# Or_ing.net
KiCad netlist of a schematic drawn in EAGLE
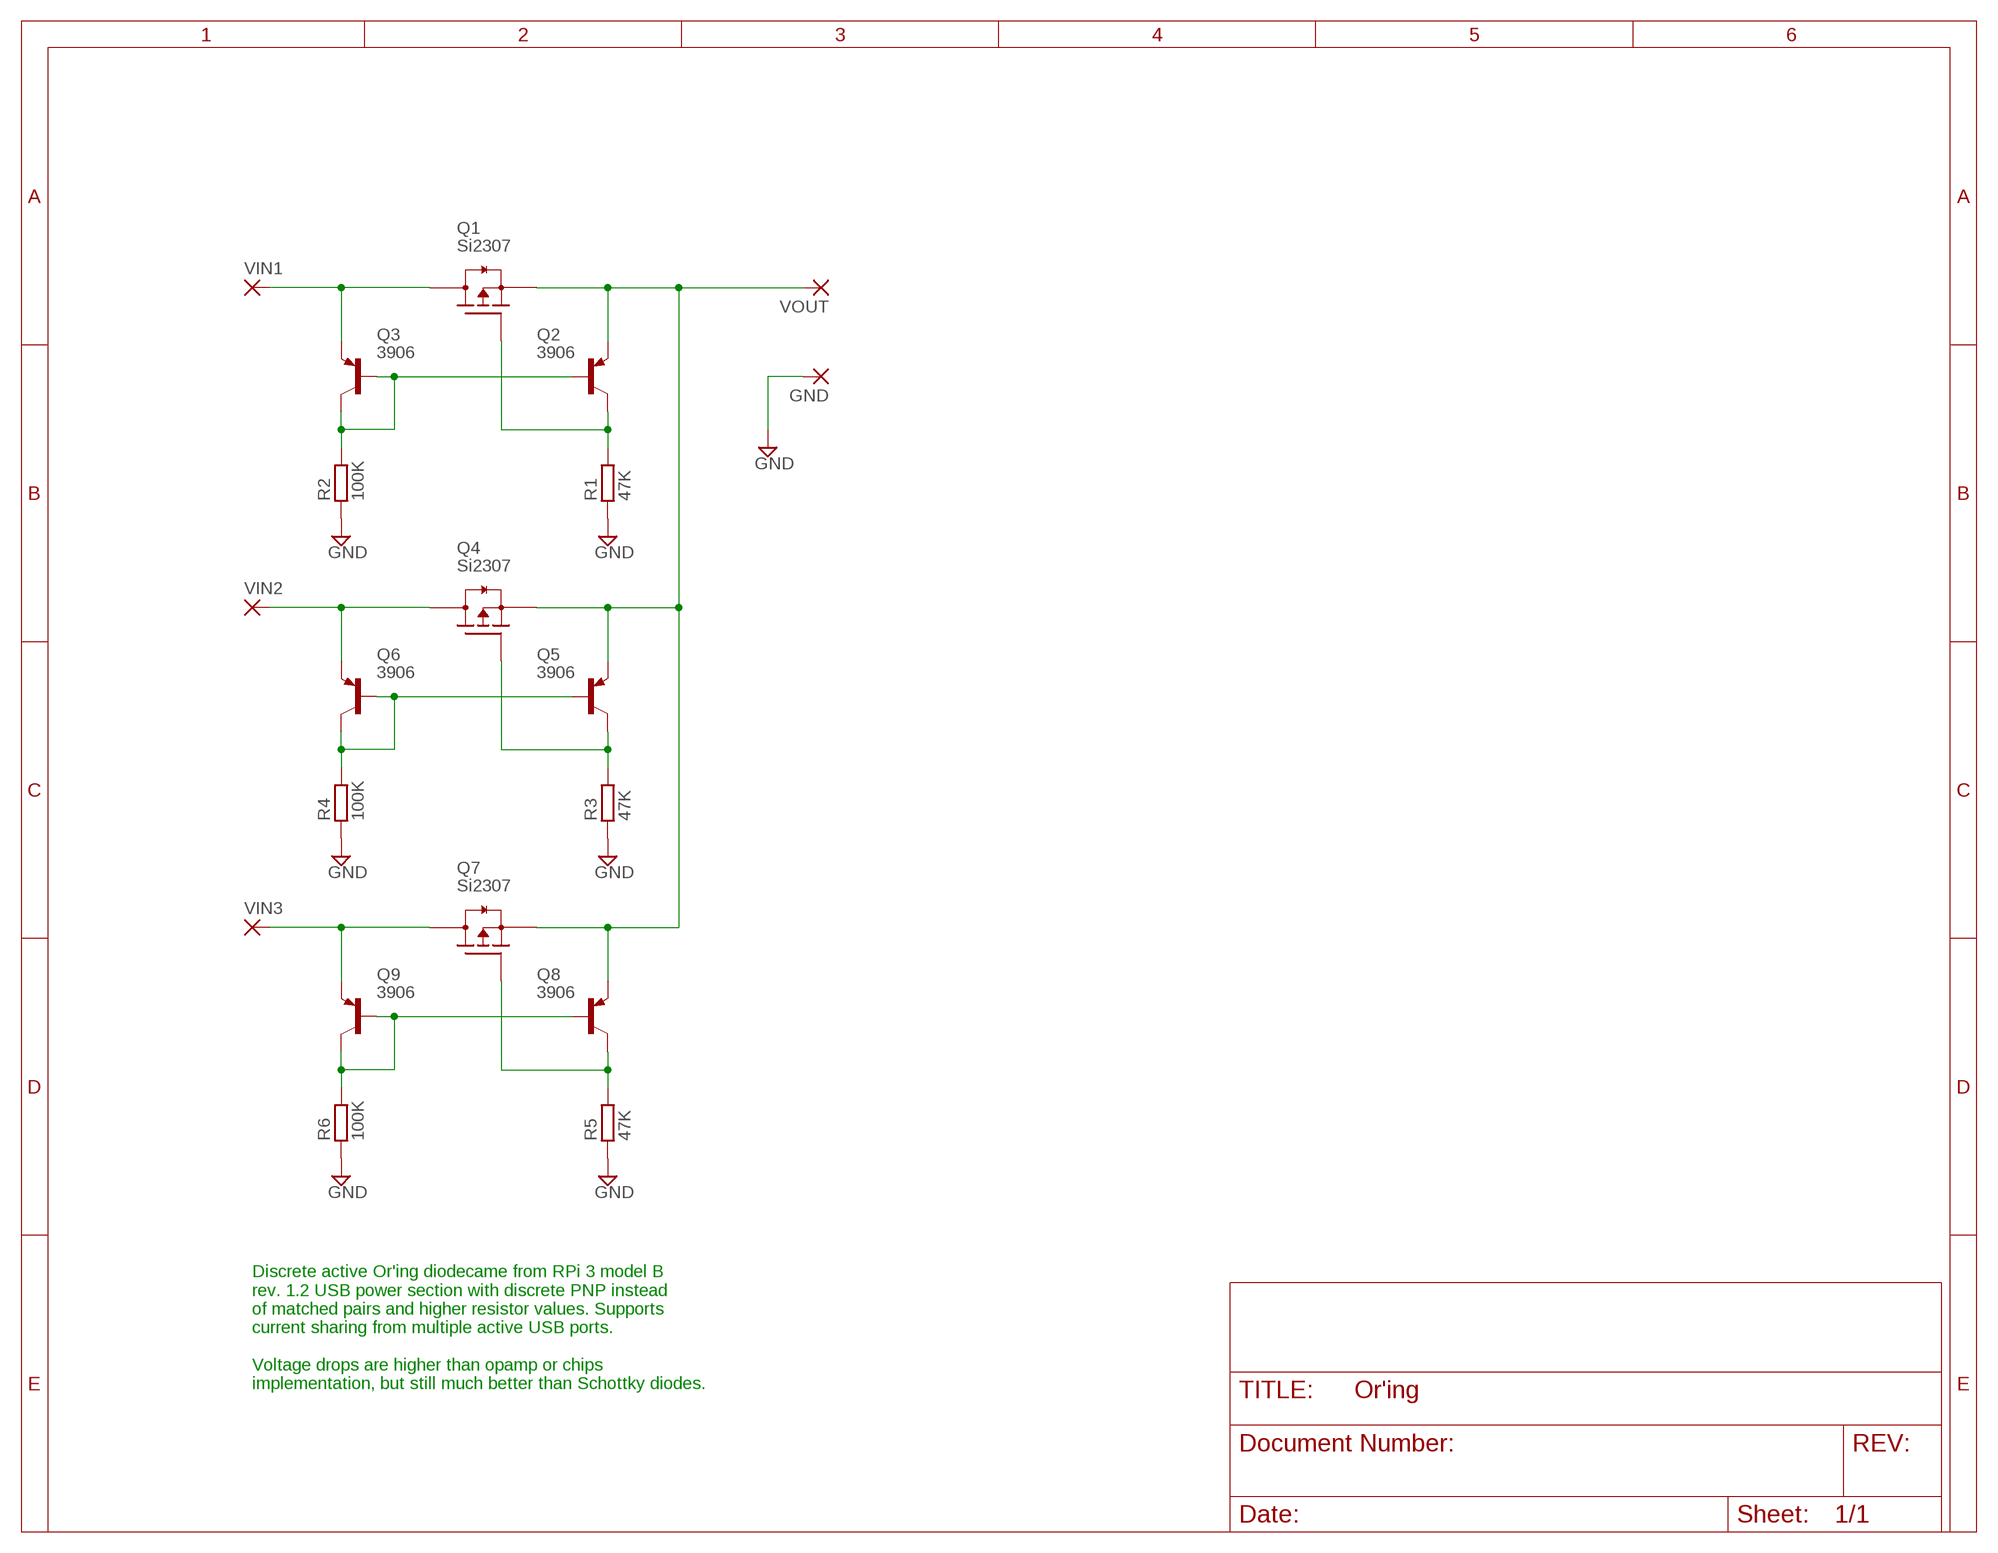
[diagram p0: schematic, sheet 1]

(export (version "E")
  (design (tool "Eeschema 10.0.6"))
  (components
    (comp (ref "GND")
      (value "SMD2")
      (footprint "eagle-import:SMD1,27-2,54")
      (libsource (lib "eagle-import") (part "SMD2"))
    )
    (comp (ref "Q1")
      (value "Si2307")
      (footprint "eagle-import:SOT95P280X135-3N")
      (libsource (lib "eagle-import") (part "MOSFET-PCH_SOT-23"))
    )
    (comp (ref "Q2")
      (value "3906")
      (footprint "eagle-import:SOT95P280X135-3N")
      (libsource (lib "eagle-import") (part "PNP_SOT-23"))
    )
    (comp (ref "Q3")
      (value "3906")
      (footprint "eagle-import:SOT95P280X135-3N")
      (libsource (lib "eagle-import") (part "PNP_SOT-23"))
    )
    (comp (ref "Q4")
      (value "Si2307")
      (footprint "eagle-import:SOT95P280X135-3N")
      (libsource (lib "eagle-import") (part "MOSFET-PCH_SOT-23"))
    )
    (comp (ref "Q5")
      (value "3906")
      (footprint "eagle-import:SOT95P280X135-3N")
      (libsource (lib "eagle-import") (part "PNP_SOT-23"))
    )
    (comp (ref "Q6")
      (value "3906")
      (footprint "eagle-import:SOT95P280X135-3N")
      (libsource (lib "eagle-import") (part "PNP_SOT-23"))
    )
    (comp (ref "Q7")
      (value "Si2307")
      (footprint "eagle-import:SOT95P280X135-3N")
      (libsource (lib "eagle-import") (part "MOSFET-PCH_SOT-23"))
    )
    (comp (ref "Q8")
      (value "3906")
      (footprint "eagle-import:SOT95P280X135-3N")
      (libsource (lib "eagle-import") (part "PNP_SOT-23"))
    )
    (comp (ref "Q9")
      (value "3906")
      (footprint "eagle-import:SOT95P280X135-3N")
      (libsource (lib "eagle-import") (part "PNP_SOT-23"))
    )
    (comp (ref "R1")
      (value "47K")
      (footprint "eagle-import:RESC1608X55N")
      (libsource (lib "eagle-import") (part "RESISTOR_0603"))
    )
    (comp (ref "R2")
      (value "100K")
      (footprint "eagle-import:RESC1608X55N")
      (libsource (lib "eagle-import") (part "RESISTOR_0603"))
    )
    (comp (ref "R3")
      (value "47K")
      (footprint "eagle-import:RESC1608X55N")
      (libsource (lib "eagle-import") (part "RESISTOR_0603"))
    )
    (comp (ref "R4")
      (value "100K")
      (footprint "eagle-import:RESC1608X55N")
      (libsource (lib "eagle-import") (part "RESISTOR_0603"))
    )
    (comp (ref "R5")
      (value "47K")
      (footprint "eagle-import:RESC1608X55N")
      (libsource (lib "eagle-import") (part "RESISTOR_0603"))
    )
    (comp (ref "R6")
      (value "100K")
      (footprint "eagle-import:RESC1608X55N")
      (libsource (lib "eagle-import") (part "RESISTOR_0603"))
    )
    (comp (ref "VIN1")
      (value "SMD2")
      (footprint "eagle-import:SMD1,27-2,54")
      (libsource (lib "eagle-import") (part "SMD2"))
    )
    (comp (ref "VIN2")
      (value "SMD2")
      (footprint "eagle-import:SMD1,27-2,54")
      (libsource (lib "eagle-import") (part "SMD2"))
    )
    (comp (ref "VIN3")
      (value "SMD2")
      (footprint "eagle-import:SMD1,27-2,54")
      (libsource (lib "eagle-import") (part "SMD2"))
    )
    (comp (ref "VOUT")
      (value "SMD2")
      (footprint "eagle-import:SMD1,27-2,54")
      (libsource (lib "eagle-import") (part "SMD2"))
    )
  )
  (nets
    (net (code "1") (name "GND") (class "Default")
      (node (ref "GND") (pin "1") (pinfunction "P_1") (pintype "passive"))
      (node (ref "R1") (pin "1") (pinfunction "1_1") (pintype "passive"))
      (node (ref "R2") (pin "1") (pinfunction "1_1") (pintype "passive"))
      (node (ref "R3") (pin "1") (pinfunction "1_1") (pintype "passive"))
      (node (ref "R4") (pin "1") (pinfunction "1_1") (pintype "passive"))
      (node (ref "R5") (pin "1") (pinfunction "1_1") (pintype "passive"))
      (node (ref "R6") (pin "1") (pinfunction "1_1") (pintype "passive"))
    )
    (net (code "2") (name "Net-(Q1-D)") (class "Default")
      (node (ref "Q1") (pin "3") (pinfunction "D_3") (pintype "passive"))
      (node (ref "Q3") (pin "2") (pinfunction "E_2") (pintype "passive"))
      (node (ref "VIN1") (pin "1") (pinfunction "P_1") (pintype "passive"))
    )
    (net (code "3") (name "Net-(Q1-G)") (class "Default")
      (node (ref "Q1") (pin "1") (pinfunction "G_1") (pintype "passive"))
      (node (ref "Q2") (pin "3") (pinfunction "C_3") (pintype "passive"))
      (node (ref "R1") (pin "2") (pinfunction "2_2") (pintype "passive"))
    )
    (net (code "4") (name "Net-(Q1-S)") (class "Default")
      (node (ref "Q1") (pin "2") (pinfunction "S_2") (pintype "passive"))
      (node (ref "Q2") (pin "2") (pinfunction "E_2") (pintype "passive"))
      (node (ref "Q4") (pin "2") (pinfunction "S_2") (pintype "passive"))
      (node (ref "Q5") (pin "2") (pinfunction "E_2") (pintype "passive"))
      (node (ref "Q7") (pin "2") (pinfunction "S_2") (pintype "passive"))
      (node (ref "Q8") (pin "2") (pinfunction "E_2") (pintype "passive"))
      (node (ref "VOUT") (pin "1") (pinfunction "P_1") (pintype "passive"))
    )
    (net (code "5") (name "Net-(Q2-B)") (class "Default")
      (node (ref "Q2") (pin "1") (pinfunction "B_1") (pintype "passive"))
      (node (ref "Q3") (pin "1") (pinfunction "B_1") (pintype "passive"))
      (node (ref "Q3") (pin "3") (pinfunction "C_3") (pintype "passive"))
      (node (ref "R2") (pin "2") (pinfunction "2_2") (pintype "passive"))
    )
    (net (code "6") (name "Net-(Q4-D)") (class "Default")
      (node (ref "Q4") (pin "3") (pinfunction "D_3") (pintype "passive"))
      (node (ref "Q6") (pin "2") (pinfunction "E_2") (pintype "passive"))
      (node (ref "VIN2") (pin "1") (pinfunction "P_1") (pintype "passive"))
    )
    (net (code "7") (name "Net-(Q4-G)") (class "Default")
      (node (ref "Q4") (pin "1") (pinfunction "G_1") (pintype "passive"))
      (node (ref "Q5") (pin "3") (pinfunction "C_3") (pintype "passive"))
      (node (ref "R3") (pin "2") (pinfunction "2_2") (pintype "passive"))
    )
    (net (code "8") (name "Net-(Q5-B)") (class "Default")
      (node (ref "Q5") (pin "1") (pinfunction "B_1") (pintype "passive"))
      (node (ref "Q6") (pin "1") (pinfunction "B_1") (pintype "passive"))
      (node (ref "Q6") (pin "3") (pinfunction "C_3") (pintype "passive"))
      (node (ref "R4") (pin "2") (pinfunction "2_2") (pintype "passive"))
    )
    (net (code "9") (name "Net-(Q7-D)") (class "Default")
      (node (ref "Q7") (pin "3") (pinfunction "D_3") (pintype "passive"))
      (node (ref "Q9") (pin "2") (pinfunction "E_2") (pintype "passive"))
      (node (ref "VIN3") (pin "1") (pinfunction "P_1") (pintype "passive"))
    )
    (net (code "10") (name "Net-(Q7-G)") (class "Default")
      (node (ref "Q7") (pin "1") (pinfunction "G_1") (pintype "passive"))
      (node (ref "Q8") (pin "3") (pinfunction "C_3") (pintype "passive"))
      (node (ref "R5") (pin "2") (pinfunction "2_2") (pintype "passive"))
    )
    (net (code "11") (name "Net-(Q8-B)") (class "Default")
      (node (ref "Q8") (pin "1") (pinfunction "B_1") (pintype "passive"))
      (node (ref "Q9") (pin "1") (pinfunction "B_1") (pintype "passive"))
      (node (ref "Q9") (pin "3") (pinfunction "C_3") (pintype "passive"))
      (node (ref "R6") (pin "2") (pinfunction "2_2") (pintype "passive"))
    )
  )
)
